# goodthopter11.net
KiCad netlist of a schematic drawn in EAGLE
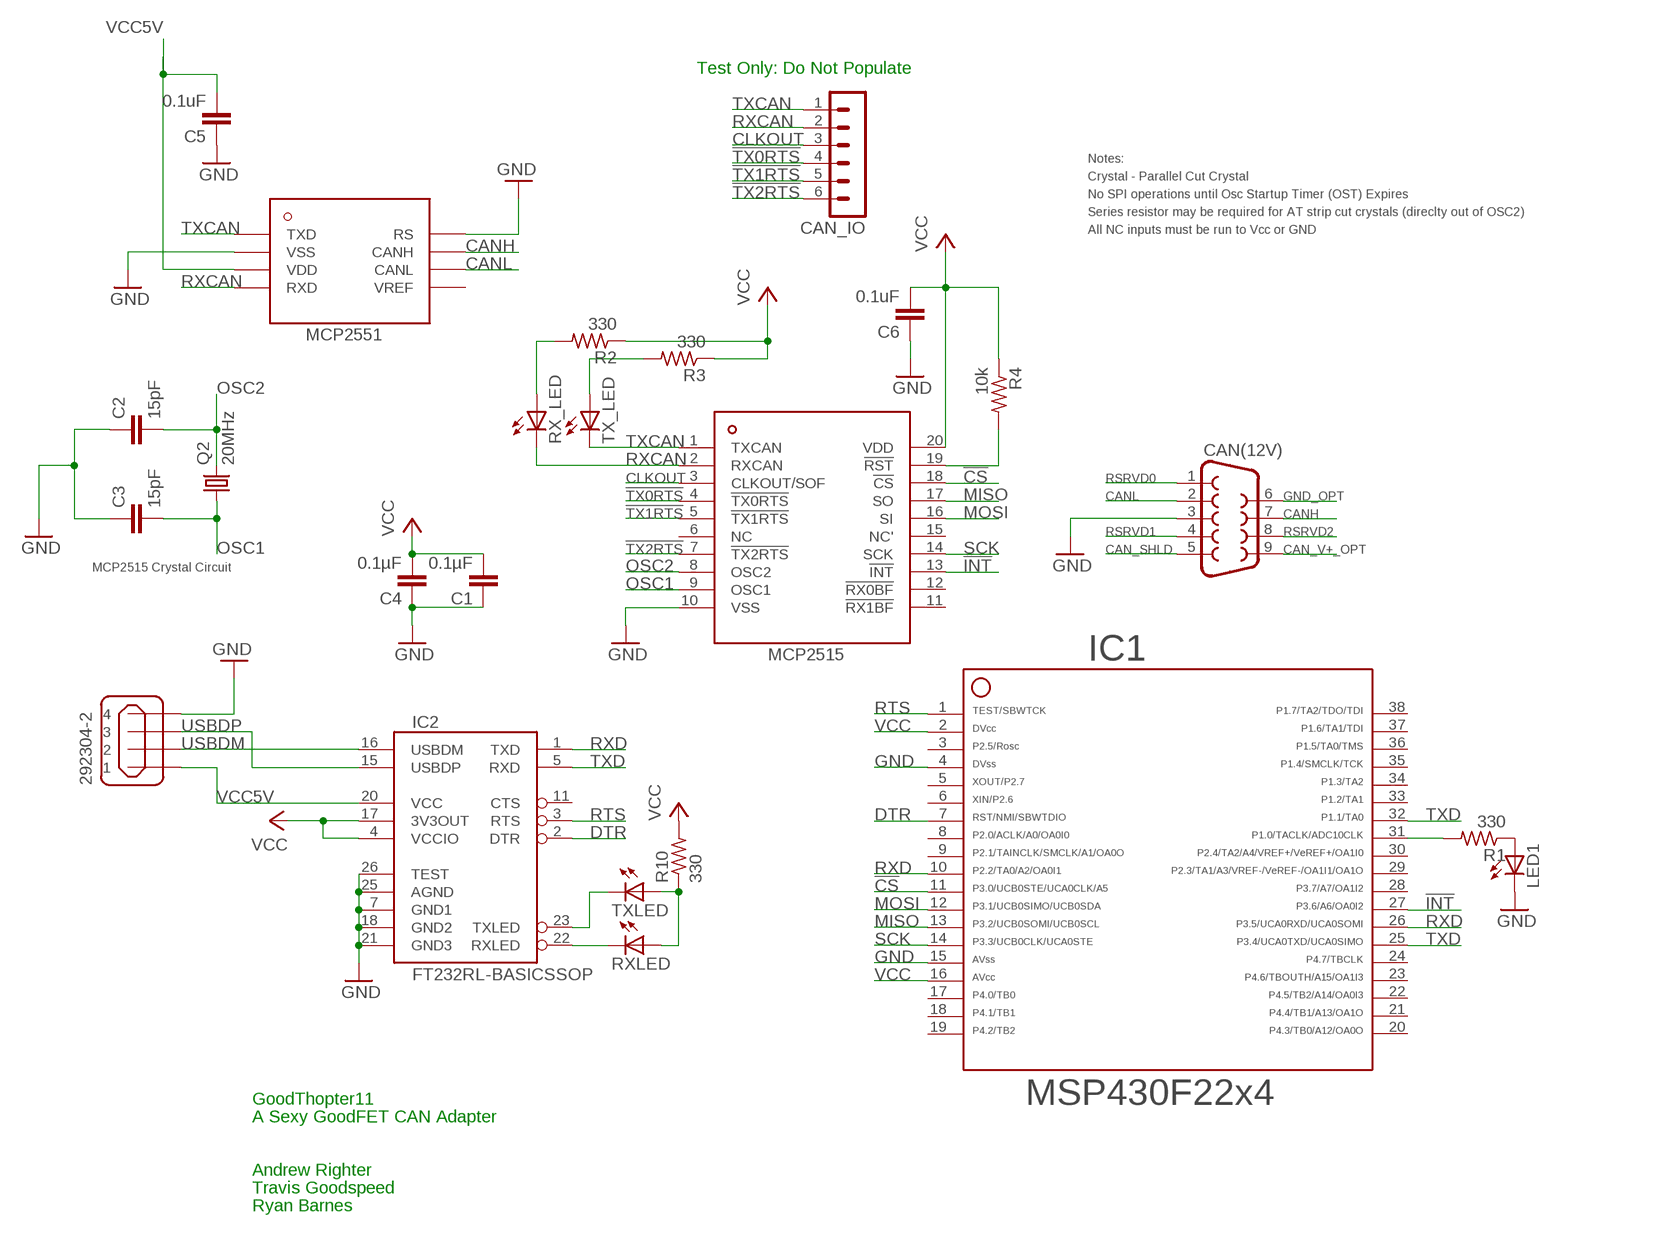
[diagram p0: schematic, sheet 1]

(export (version "E")
  (design (tool "Eeschema 10.0.6"))
  (components
    (comp (ref "292304-2")
      (value "MINI-USB_4P-292304-2")
      (footprint "eagle-import:85-32004-10X")
      (libsource (lib "eagle-import") (part "MINI-USB_4P-292304-2"))
    )
    (comp (ref "C1")
      (value "0.1µF")
      (footprint "eagle-import:C0603")
      (libsource (lib "eagle-import") (part "C-EUC0603"))
    )
    (comp (ref "C2")
      (value "15pF")
      (footprint "eagle-import:C0603")
      (libsource (lib "eagle-import") (part "C-EUC0603"))
    )
    (comp (ref "C3")
      (value "15pF")
      (footprint "eagle-import:C0603")
      (libsource (lib "eagle-import") (part "C-EUC0603"))
    )
    (comp (ref "C4")
      (value "0.1µF")
      (footprint "eagle-import:C0603")
      (libsource (lib "eagle-import") (part "C-EUC0603"))
    )
    (comp (ref "C5")
      (value "0.1uF")
      (footprint "eagle-import:C0603")
      (libsource (lib "eagle-import") (part "C-EUC0603"))
    )
    (comp (ref "C6")
      (value "0.1uF")
      (footprint "eagle-import:C0603")
      (libsource (lib "eagle-import") (part "C-EUC0603"))
    )
    (comp (ref "CAN(12V)")
      (value "DB9MALE")
      (footprint "eagle-import:DB9_MALE")
      (libsource (lib "eagle-import") (part "DB9MALE"))
    )
    (comp (ref "CAN_IO")
      (value "MA06-1")
      (footprint "eagle-import:MA06-1")
      (libsource (lib "eagle-import") (part "MA06-1"))
    )
    (comp (ref "IC1")
      (value "F22X4---DA38")
      (footprint "eagle-import:DA38")
      (libsource (lib "eagle-import") (part "F22X4---DA38"))
    )
    (comp (ref "IC2")
      (value "FT232RL-BASICSSOP")
      (footprint "eagle-import:SSOP28DB")
      (libsource (lib "eagle-import") (part "FT232RL-BASICSSOP"))
    )
    (comp (ref "LED1")
      (value "LEDCHIP-LED0603")
      (footprint "eagle-import:CHIP-LED0603")
      (libsource (lib "eagle-import") (part "LEDCHIP-LED0603"))
    )
    (comp (ref "Q2")
      (value "20MHz")
      (footprint "eagle-import:HC49UP")
      (libsource (lib "eagle-import") (part "CRYSTALHC49UP"))
    )
    (comp (ref "R1")
      (value "330")
      (footprint "eagle-import:R0603")
      (libsource (lib "eagle-import") (part "R-US_R0603"))
    )
    (comp (ref "R2")
      (value "330")
      (footprint "eagle-import:R0603")
      (libsource (lib "eagle-import") (part "R-US_R0603"))
    )
    (comp (ref "R3")
      (value "330")
      (footprint "eagle-import:R0603")
      (libsource (lib "eagle-import") (part "R-US_R0603"))
    )
    (comp (ref "R4")
      (value "10k")
      (footprint "eagle-import:R0603")
      (libsource (lib "eagle-import") (part "R-US_R0603"))
    )
    (comp (ref "R10")
      (value "330")
      (footprint "eagle-import:R0603")
      (libsource (lib "eagle-import") (part "R-US_R0603"))
    )
    (comp (ref "RXLED")
      (value "LEDCHIP-LED0603")
      (footprint "eagle-import:CHIP-LED0603")
      (libsource (lib "eagle-import") (part "LEDCHIP-LED0603"))
    )
    (comp (ref "RX_LED")
      (value "LEDCHIP-LED0603")
      (footprint "eagle-import:CHIP-LED0603")
      (libsource (lib "eagle-import") (part "LEDCHIP-LED0603"))
    )
    (comp (ref "TXLED")
      (value "LEDCHIP-LED0603")
      (footprint "eagle-import:CHIP-LED0603")
      (libsource (lib "eagle-import") (part "LEDCHIP-LED0603"))
    )
    (comp (ref "TX_LED")
      (value "LEDCHIP-LED0603")
      (footprint "eagle-import:CHIP-LED0603")
      (libsource (lib "eagle-import") (part "LEDCHIP-LED0603"))
    )
    (comp (ref "U$1")
      (value "MCP2515")
      (footprint "eagle-import:TSSOP20")
      (libsource (lib "eagle-import") (part "MCP2515"))
    )
    (comp (ref "U$2")
      (value "MCP2551")
      (footprint "eagle-import:SOIC-8")
      (libsource (lib "eagle-import") (part "MCP2551"))
    )
  )
  (nets
    (net (code "1") (name "/CANH") (class "Default")
      (node (ref "CAN(12V)") (pin "7") (pinfunction "7_7") (pintype "passive"))
      (node (ref "U$2") (pin "CANH") (pinfunction "CANH_CANH") (pintype "bidirectional"))
    )
    (net (code "2") (name "/CANL") (class "Default")
      (node (ref "CAN(12V)") (pin "2") (pinfunction "2_2") (pintype "passive"))
      (node (ref "U$2") (pin "CANL") (pinfunction "CANL_CANL") (pintype "bidirectional"))
    )
    (net (code "3") (name "/CAN_SHLD") (class "Default")
      (node (ref "CAN(12V)") (pin "5") (pinfunction "5_5") (pintype "passive"))
    )
    (net (code "4") (name "/CAN_V+_OPT") (class "Default")
      (node (ref "CAN(12V)") (pin "9") (pinfunction "9_9") (pintype "passive"))
    )
    (net (code "5") (name "/CLKOUT") (class "Default")
      (node (ref "CAN_IO") (pin "3") (pinfunction "3_3") (pintype "passive"))
      (node (ref "U$1") (pin "3") (pinfunction "CLKOUT/SOF_3") (pintype "bidirectional"))
    )
    (net (code "6") (name "/DTR") (class "Default")
      (node (ref "IC1") (pin "7") (pinfunction "7_7") (pintype "bidirectional"))
      (node (ref "IC2") (pin "2") (pinfunction "DTR_2") (pintype "bidirectional"))
    )
    (net (code "7") (name "/GND_OPT") (class "Default")
      (node (ref "CAN(12V)") (pin "6") (pinfunction "6_6") (pintype "passive"))
    )
    (net (code "8") (name "/MISO") (class "Default")
      (node (ref "IC1") (pin "13") (pinfunction "13_13") (pintype "bidirectional"))
      (node (ref "U$1") (pin "17") (pinfunction "SO_17") (pintype "bidirectional"))
    )
    (net (code "9") (name "/MOSI") (class "Default")
      (node (ref "IC1") (pin "12") (pinfunction "12_12") (pintype "bidirectional"))
      (node (ref "U$1") (pin "16") (pinfunction "SI_16") (pintype "bidirectional"))
    )
    (net (code "10") (name "/OSC1") (class "Default")
      (node (ref "C3") (pin "2") (pinfunction "2_2") (pintype "passive"))
      (node (ref "Q2") (pin "1") (pinfunction "1_1") (pintype "passive"))
      (node (ref "U$1") (pin "9") (pinfunction "OSC1_9") (pintype "bidirectional"))
    )
    (net (code "11") (name "/OSC2") (class "Default")
      (node (ref "C2") (pin "2") (pinfunction "2_2") (pintype "passive"))
      (node (ref "Q2") (pin "2") (pinfunction "2_2") (pintype "passive"))
      (node (ref "U$1") (pin "8") (pinfunction "OSC2_8") (pintype "bidirectional"))
    )
    (net (code "12") (name "/RSRVD0") (class "Default")
      (node (ref "CAN(12V)") (pin "1") (pinfunction "1_1") (pintype "passive"))
    )
    (net (code "13") (name "/RSRVD1") (class "Default")
      (node (ref "CAN(12V)") (pin "4") (pinfunction "4_4") (pintype "passive"))
    )
    (net (code "14") (name "/RSRVD2") (class "Default")
      (node (ref "CAN(12V)") (pin "8") (pinfunction "8_8") (pintype "passive"))
    )
    (net (code "15") (name "/RTS") (class "Default")
      (node (ref "IC1") (pin "1") (pinfunction "1_1") (pintype "input"))
      (node (ref "IC2") (pin "3") (pinfunction "RTS_3") (pintype "bidirectional"))
    )
    (net (code "16") (name "/RXCAN") (class "Default")
      (node (ref "CAN_IO") (pin "2") (pinfunction "2_2") (pintype "passive"))
      (node (ref "RX_LED") (pin "C") (pinfunction "C_C") (pintype "passive"))
      (node (ref "U$1") (pin "2") (pinfunction "RXCAN_2") (pintype "bidirectional"))
      (node (ref "U$2") (pin "RXD") (pinfunction "RXD_RXD") (pintype "bidirectional"))
    )
    (net (code "17") (name "/RXD") (class "Default")
      (node (ref "IC1") (pin "10") (pinfunction "10_10") (pintype "bidirectional"))
      (node (ref "IC1") (pin "26") (pinfunction "26_26") (pintype "bidirectional"))
      (node (ref "IC2") (pin "1") (pinfunction "TXD_1") (pintype "output"))
    )
    (net (code "18") (name "/SCK") (class "Default")
      (node (ref "IC1") (pin "14") (pinfunction "14_14") (pintype "bidirectional"))
      (node (ref "U$1") (pin "14") (pinfunction "SCK_14") (pintype "bidirectional"))
    )
    (net (code "19") (name "/TXCAN") (class "Default")
      (node (ref "CAN_IO") (pin "1") (pinfunction "1_1") (pintype "passive"))
      (node (ref "TX_LED") (pin "C") (pinfunction "C_C") (pintype "passive"))
      (node (ref "U$1") (pin "1") (pinfunction "TXCAN_1") (pintype "bidirectional"))
      (node (ref "U$2") (pin "TXD") (pinfunction "TXD_TXD") (pintype "bidirectional"))
    )
    (net (code "20") (name "/TXD") (class "Default")
      (node (ref "IC1") (pin "25") (pinfunction "25_25") (pintype "bidirectional"))
      (node (ref "IC1") (pin "32") (pinfunction "32_32") (pintype "bidirectional"))
      (node (ref "IC2") (pin "5") (pinfunction "RXD_5") (pintype "input"))
    )
    (net (code "21") (name "/USBDM") (class "Default")
      (node (ref "292304-2") (pin "2") (pinfunction "2_2") (pintype "passive"))
      (node (ref "IC2") (pin "16") (pinfunction "USBDM_16") (pintype "bidirectional"))
    )
    (net (code "22") (name "/USBDP") (class "Default")
      (node (ref "292304-2") (pin "3") (pinfunction "3_3") (pintype "passive"))
      (node (ref "IC2") (pin "15") (pinfunction "USBDP_15") (pintype "bidirectional"))
    )
    (net (code "23") (name "/VCC5V") (class "Default")
      (node (ref "292304-2") (pin "1") (pinfunction "1_1") (pintype "passive"))
      (node (ref "C5") (pin "2") (pinfunction "2_2") (pintype "passive"))
      (node (ref "IC2") (pin "20") (pinfunction "VCC_20") (pintype "power_in"))
      (node (ref "U$2") (pin "VDD") (pinfunction "VDD_VDD") (pintype "bidirectional"))
    )
    (net (code "24") (name "/~{CS}") (class "Default")
      (node (ref "IC1") (pin "11") (pinfunction "11_11") (pintype "bidirectional"))
      (node (ref "U$1") (pin "18") (pinfunction "~{CS}_18") (pintype "bidirectional"))
    )
    (net (code "25") (name "/~{INT}") (class "Default")
      (node (ref "IC1") (pin "27") (pinfunction "27_27") (pintype "bidirectional"))
      (node (ref "U$1") (pin "13") (pinfunction "~{INT}_13") (pintype "bidirectional"))
    )
    (net (code "26") (name "/~{TX0RTS}") (class "Default")
      (node (ref "CAN_IO") (pin "4") (pinfunction "4_4") (pintype "passive"))
      (node (ref "U$1") (pin "4") (pinfunction "~{TX0RTS}_4") (pintype "bidirectional"))
    )
    (net (code "27") (name "/~{TX1RTS}") (class "Default")
      (node (ref "CAN_IO") (pin "5") (pinfunction "5_5") (pintype "passive"))
      (node (ref "U$1") (pin "5") (pinfunction "~{TX1RTS}_5") (pintype "bidirectional"))
    )
    (net (code "28") (name "/~{TX2RTS}") (class "Default")
      (node (ref "CAN_IO") (pin "6") (pinfunction "6_6") (pintype "passive"))
      (node (ref "U$1") (pin "7") (pinfunction "~{TX2RTS}_7") (pintype "bidirectional"))
    )
    (net (code "29") (name "GND") (class "Default")
      (node (ref "292304-2") (pin "4") (pinfunction "4_4") (pintype "passive"))
      (node (ref "C1") (pin "1") (pinfunction "1_1") (pintype "passive"))
      (node (ref "C2") (pin "1") (pinfunction "1_1") (pintype "passive"))
      (node (ref "C3") (pin "1") (pinfunction "1_1") (pintype "passive"))
      (node (ref "C4") (pin "1") (pinfunction "1_1") (pintype "passive"))
      (node (ref "C5") (pin "1") (pinfunction "1_1") (pintype "passive"))
      (node (ref "C6") (pin "1") (pinfunction "1_1") (pintype "passive"))
      (node (ref "CAN(12V)") (pin "3") (pinfunction "3_3") (pintype "passive"))
      (node (ref "IC1") (pin "15") (pinfunction "15_15") (pintype "power_in"))
      (node (ref "IC1") (pin "4") (pinfunction "4_4") (pintype "power_in"))
      (node (ref "IC2") (pin "18") (pinfunction "GND2_18") (pintype "power_in"))
      (node (ref "IC2") (pin "21") (pinfunction "GND3_21") (pintype "power_in"))
      (node (ref "IC2") (pin "25") (pinfunction "AGND_25") (pintype "power_in"))
      (node (ref "IC2") (pin "26") (pinfunction "TEST_26") (pintype "input"))
      (node (ref "IC2") (pin "7") (pinfunction "GND1_7") (pintype "power_in"))
      (node (ref "LED1") (pin "C") (pinfunction "C_C") (pintype "passive"))
      (node (ref "U$1") (pin "10") (pinfunction "VSS_10") (pintype "bidirectional"))
      (node (ref "U$2") (pin "RS") (pinfunction "RS_RS") (pintype "bidirectional"))
      (node (ref "U$2") (pin "VSS") (pinfunction "VSS_VSS") (pintype "bidirectional"))
    )
    (net (code "30") (name "Net-(IC1-Pad31)") (class "Default")
      (node (ref "IC1") (pin "31") (pinfunction "31_31") (pintype "bidirectional"))
      (node (ref "R1") (pin "2") (pinfunction "2_2") (pintype "passive"))
    )
    (net (code "31") (name "Net-(IC2-RXLED)") (class "Default")
      (node (ref "IC2") (pin "22") (pinfunction "RXLED_22") (pintype "bidirectional"))
      (node (ref "RXLED") (pin "C") (pinfunction "C_C") (pintype "passive"))
    )
    (net (code "32") (name "Net-(IC2-TXLED)") (class "Default")
      (node (ref "IC2") (pin "23") (pinfunction "TXLED_23") (pintype "bidirectional"))
      (node (ref "TXLED") (pin "C") (pinfunction "C_C") (pintype "passive"))
    )
    (net (code "33") (name "Net-(LED1-PadA)") (class "Default")
      (node (ref "LED1") (pin "A") (pinfunction "A_A") (pintype "passive"))
      (node (ref "R1") (pin "1") (pinfunction "1_1") (pintype "passive"))
    )
    (net (code "34") (name "Net-(R2-Pad2)") (class "Default")
      (node (ref "R2") (pin "2") (pinfunction "2_2") (pintype "passive"))
      (node (ref "RX_LED") (pin "A") (pinfunction "A_A") (pintype "passive"))
    )
    (net (code "35") (name "Net-(R3-Pad2)") (class "Default")
      (node (ref "R3") (pin "2") (pinfunction "2_2") (pintype "passive"))
      (node (ref "TX_LED") (pin "A") (pinfunction "A_A") (pintype "passive"))
    )
    (net (code "36") (name "Net-(R10-Pad1)") (class "Default")
      (node (ref "R10") (pin "1") (pinfunction "1_1") (pintype "passive"))
      (node (ref "RXLED") (pin "A") (pinfunction "A_A") (pintype "passive"))
      (node (ref "TXLED") (pin "A") (pinfunction "A_A") (pintype "passive"))
    )
    (net (code "37") (name "Net-(U$1-~{RST})") (class "Default")
      (node (ref "R4") (pin "2") (pinfunction "2_2") (pintype "passive"))
      (node (ref "U$1") (pin "19") (pinfunction "~{RST}_19") (pintype "bidirectional"))
    )
    (net (code "38") (name "VCC") (class "Default")
      (node (ref "C1") (pin "2") (pinfunction "2_2") (pintype "passive"))
      (node (ref "C4") (pin "2") (pinfunction "2_2") (pintype "passive"))
      (node (ref "C6") (pin "2") (pinfunction "2_2") (pintype "passive"))
      (node (ref "IC1") (pin "16") (pinfunction "16_16") (pintype "power_in"))
      (node (ref "IC1") (pin "2") (pinfunction "2_2") (pintype "power_in"))
      (node (ref "IC2") (pin "17") (pinfunction "3V3OUT_17") (pintype "output"))
      (node (ref "IC2") (pin "4") (pinfunction "VCCIO_4") (pintype "power_in"))
      (node (ref "R10") (pin "2") (pinfunction "2_2") (pintype "passive"))
      (node (ref "R2") (pin "1") (pinfunction "1_1") (pintype "passive"))
      (node (ref "R3") (pin "1") (pinfunction "1_1") (pintype "passive"))
      (node (ref "R4") (pin "1") (pinfunction "1_1") (pintype "passive"))
      (node (ref "U$1") (pin "20") (pinfunction "VDD_20") (pintype "bidirectional"))
    )
    (net (code "39") (name "unconnected-(IC1-Pad3)") (class "Default")
      (node (ref "IC1") (pin "3") (pinfunction "3_3") (pintype "bidirectional"))
    )
    (net (code "40") (name "unconnected-(IC1-Pad5)") (class "Default")
      (node (ref "IC1") (pin "5") (pinfunction "5_5") (pintype "bidirectional"))
    )
    (net (code "41") (name "unconnected-(IC1-Pad6)") (class "Default")
      (node (ref "IC1") (pin "6") (pinfunction "6_6") (pintype "bidirectional"))
    )
    (net (code "42") (name "unconnected-(IC1-Pad8)") (class "Default")
      (node (ref "IC1") (pin "8") (pinfunction "8_8") (pintype "bidirectional"))
    )
    (net (code "43") (name "unconnected-(IC1-Pad9)") (class "Default")
      (node (ref "IC1") (pin "9") (pinfunction "9_9") (pintype "bidirectional"))
    )
    (net (code "44") (name "unconnected-(IC1-Pad17)") (class "Default")
      (node (ref "IC1") (pin "17") (pinfunction "17_17") (pintype "bidirectional"))
    )
    (net (code "45") (name "unconnected-(IC1-Pad18)") (class "Default")
      (node (ref "IC1") (pin "18") (pinfunction "18_18") (pintype "bidirectional"))
    )
    (net (code "46") (name "unconnected-(IC1-Pad19)") (class "Default")
      (node (ref "IC1") (pin "19") (pinfunction "19_19") (pintype "bidirectional"))
    )
    (net (code "47") (name "unconnected-(IC1-Pad20)") (class "Default")
      (node (ref "IC1") (pin "20") (pinfunction "20_20") (pintype "bidirectional"))
    )
    (net (code "48") (name "unconnected-(IC1-Pad21)") (class "Default")
      (node (ref "IC1") (pin "21") (pinfunction "21_21") (pintype "bidirectional"))
    )
    (net (code "49") (name "unconnected-(IC1-Pad22)") (class "Default")
      (node (ref "IC1") (pin "22") (pinfunction "22_22") (pintype "bidirectional"))
    )
    (net (code "50") (name "unconnected-(IC1-Pad23)") (class "Default")
      (node (ref "IC1") (pin "23") (pinfunction "23_23") (pintype "bidirectional"))
    )
    (net (code "51") (name "unconnected-(IC1-Pad24)") (class "Default")
      (node (ref "IC1") (pin "24") (pinfunction "24_24") (pintype "bidirectional"))
    )
    (net (code "52") (name "unconnected-(IC1-Pad28)") (class "Default")
      (node (ref "IC1") (pin "28") (pinfunction "28_28") (pintype "bidirectional"))
    )
    (net (code "53") (name "unconnected-(IC1-Pad29)") (class "Default")
      (node (ref "IC1") (pin "29") (pinfunction "29_29") (pintype "bidirectional"))
    )
    (net (code "54") (name "unconnected-(IC1-Pad30)") (class "Default")
      (node (ref "IC1") (pin "30") (pinfunction "30_30") (pintype "bidirectional"))
    )
    (net (code "55") (name "unconnected-(IC1-Pad33)") (class "Default")
      (node (ref "IC1") (pin "33") (pinfunction "33_33") (pintype "bidirectional"))
    )
    (net (code "56") (name "unconnected-(IC1-Pad34)") (class "Default")
      (node (ref "IC1") (pin "34") (pinfunction "34_34") (pintype "bidirectional"))
    )
    (net (code "57") (name "unconnected-(IC1-Pad35)") (class "Default")
      (node (ref "IC1") (pin "35") (pinfunction "35_35") (pintype "bidirectional"))
    )
    (net (code "58") (name "unconnected-(IC1-Pad36)") (class "Default")
      (node (ref "IC1") (pin "36") (pinfunction "36_36") (pintype "bidirectional"))
    )
    (net (code "59") (name "unconnected-(IC1-Pad37)") (class "Default")
      (node (ref "IC1") (pin "37") (pinfunction "37_37") (pintype "bidirectional"))
    )
    (net (code "60") (name "unconnected-(IC1-Pad38)") (class "Default")
      (node (ref "IC1") (pin "38") (pinfunction "38_38") (pintype "bidirectional"))
    )
    (net (code "61") (name "unconnected-(IC2-CTS-Pad11)") (class "Default")
      (node (ref "IC2") (pin "11") (pinfunction "CTS_11") (pintype "bidirectional"))
    )
    (net (code "62") (name "unconnected-(U$1-NC'-Pad15)") (class "Default")
      (node (ref "U$1") (pin "15") (pinfunction "NC'_15") (pintype "bidirectional"))
    )
    (net (code "63") (name "unconnected-(U$1-NC-Pad6)") (class "Default")
      (node (ref "U$1") (pin "6") (pinfunction "NC_6") (pintype "bidirectional"))
    )
    (net (code "64") (name "unconnected-(U$1-~{RX0BF}-Pad12)") (class "Default")
      (node (ref "U$1") (pin "12") (pinfunction "~{RX0BF}_12") (pintype "bidirectional"))
    )
    (net (code "65") (name "unconnected-(U$1-~{RX1BF}-Pad11)") (class "Default")
      (node (ref "U$1") (pin "11") (pinfunction "~{RX1BF}_11") (pintype "bidirectional"))
    )
    (net (code "66") (name "unconnected-(U$2-PadVREF)") (class "Default")
      (node (ref "U$2") (pin "VREF") (pinfunction "VREF_VREF") (pintype "bidirectional"))
    )
  )
)
